# MINI_SAM_D51_018.net
KiCad netlist of a schematic drawn in EAGLE
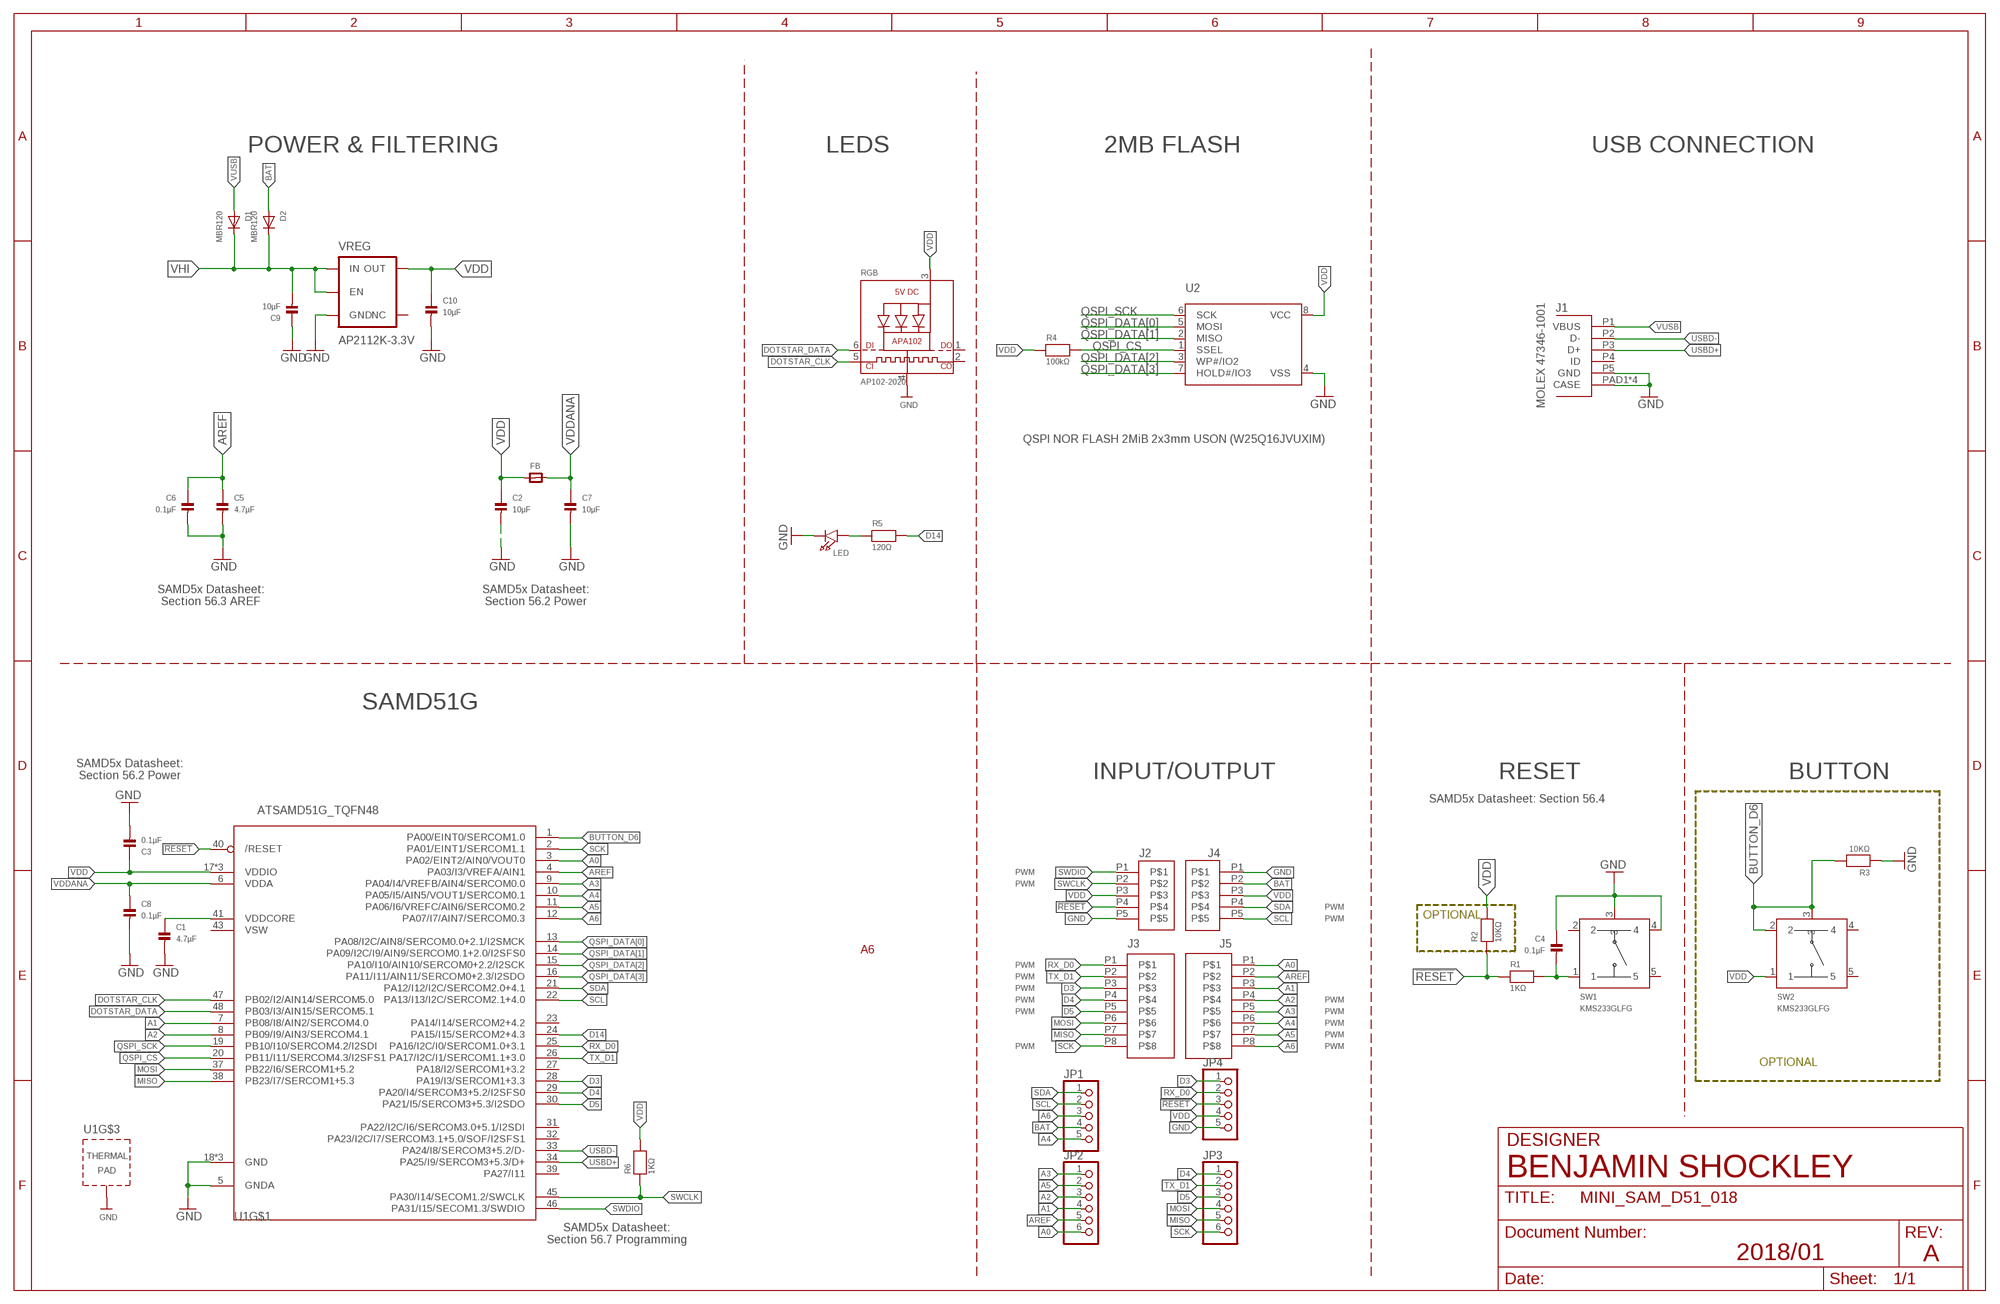
[diagram p0: schematic, sheet 1]

(export (version "E")
  (design (tool "Eeschema 10.0.6"))
  (components
    (comp (ref "C1")
      (value "4.7µF")
      (footprint "eagle-import:_0603MP")
      (libsource (lib "eagle-import") (part "CAP_CERAMIC_0603MP"))
    )
    (comp (ref "C2")
      (value "10µF")
      (footprint "eagle-import:_0603MP")
      (libsource (lib "eagle-import") (part "CAP_CERAMIC_0603MP"))
    )
    (comp (ref "C3")
      (value "0.1µF")
      (footprint "eagle-import:_0603MP")
      (libsource (lib "eagle-import") (part "CAP_CERAMIC_0603MP"))
    )
    (comp (ref "C4")
      (value "0.1µF")
      (footprint "eagle-import:_0603MP")
      (libsource (lib "eagle-import") (part "CAP_CERAMIC_0603MP"))
    )
    (comp (ref "C5")
      (value "4.7µF")
      (footprint "eagle-import:_0603MP")
      (libsource (lib "eagle-import") (part "CAP_CERAMIC_0603MP"))
    )
    (comp (ref "C6")
      (value "0.1µF")
      (footprint "eagle-import:_0603MP")
      (libsource (lib "eagle-import") (part "CAP_CERAMIC_0603MP"))
    )
    (comp (ref "C7")
      (value "10µF")
      (footprint "eagle-import:_0603MP")
      (libsource (lib "eagle-import") (part "CAP_CERAMIC_0603MP"))
    )
    (comp (ref "C8")
      (value "0.1µF")
      (footprint "eagle-import:_0603MP")
      (libsource (lib "eagle-import") (part "CAP_CERAMIC_0603MP"))
    )
    (comp (ref "C9")
      (value "10µF")
      (footprint "eagle-import:_0603MP")
      (libsource (lib "eagle-import") (part "CAP_CERAMIC_0603MP"))
    )
    (comp (ref "C10")
      (value "10µF")
      (footprint "eagle-import:_0603MP")
      (libsource (lib "eagle-import") (part "CAP_CERAMIC_0603MP"))
    )
    (comp (ref "D1")
      (value "MBR120")
      (footprint "eagle-import:SOD-123FL")
      (libsource (lib "eagle-import") (part "DIODE_SOD-123FL"))
    )
    (comp (ref "D2")
      (value "MBR120")
      (footprint "eagle-import:SOD-123FL")
      (libsource (lib "eagle-import") (part "DIODE_SOD-123FL"))
    )
    (comp (ref "FB")
      (value "Impedence: 50 ohm @ 20 MHz, 220 Ohm @ 100 MHz; low DC resistance")
      (footprint "eagle-import:_0603MP")
      (libsource (lib "eagle-import") (part "FERRITE_0603MP"))
    )
    (comp (ref "J1")
      (value "MOLEX_47346-100147346")
      (footprint "eagle-import:MOLEX_47346-1001")
      (libsource (lib "eagle-import") (part "MOLEX_47346-100147346"))
    )
    (comp (ref "J2")
      (value "1X5_HEADER_1.27MMCAST")
      (footprint "eagle-import:1X5_HEADER_1.27MM_CASTELLATED")
      (libsource (lib "eagle-import") (part "1X5_HEADER_1.27MMCAST"))
    )
    (comp (ref "J3")
      (value "1X8_HEADER_1.27MMCAST")
      (footprint "eagle-import:1X8_HEADER_1.27MM_CASTELLATED")
      (libsource (lib "eagle-import") (part "1X8_HEADER_1.27MMCAST"))
    )
    (comp (ref "J4")
      (value "1X5_HEADER_1.27MMCAST")
      (footprint "eagle-import:1X5_HEADER_1.27MM_CASTELLATED")
      (libsource (lib "eagle-import") (part "1X5_HEADER_1.27MMCAST"))
    )
    (comp (ref "J5")
      (value "1X8_HEADER_1.27MMCAST")
      (footprint "eagle-import:1X8_HEADER_1.27MM_CASTELLATED")
      (libsource (lib "eagle-import") (part "1X8_HEADER_1.27MMCAST"))
    )
    (comp (ref "JP1")
      (value "PINHD-1X51X05_SMT")
      (footprint "eagle-import:1X05_SMT")
      (libsource (lib "eagle-import") (part "PINHD-1X51X05_SMT"))
    )
    (comp (ref "JP2")
      (value "PINHD-1X61X06_SMT")
      (footprint "eagle-import:1X06_SMT")
      (libsource (lib "eagle-import") (part "PINHD-1X61X06_SMT"))
    )
    (comp (ref "JP3")
      (value "PINHD-1X6REV")
      (footprint "eagle-import:1X06_SMT_REV")
      (libsource (lib "eagle-import") (part "PINHD-1X6REV"))
    )
    (comp (ref "JP4")
      (value "PINHD-1X51X05_SMT")
      (footprint "eagle-import:1X05_SMT")
      (libsource (lib "eagle-import") (part "PINHD-1X51X05_SMT"))
    )
    (comp (ref "LED")
      (value "VLRK31Q1R2-GS08")
      (footprint "eagle-import:REVERSE_MOUNT_LED")
      (libsource (lib "eagle-import") (part "REVERSEMOUNTLED"))
    )
    (comp (ref "R1")
      (value "1KΩ")
      (footprint "eagle-import:_0603MP")
      (libsource (lib "eagle-import") (part "RESISTOR_0603MP"))
    )
    (comp (ref "R2")
      (value "10KΩ")
      (footprint "eagle-import:_0603MP")
      (libsource (lib "eagle-import") (part "RESISTOR_0603MP"))
    )
    (comp (ref "R3")
      (value "10KΩ")
      (footprint "eagle-import:_0603MP")
      (libsource (lib "eagle-import") (part "RESISTOR_0603MP"))
    )
    (comp (ref "R4")
      (value "100kΩ")
      (footprint "eagle-import:_0603MP")
      (libsource (lib "eagle-import") (part "RESISTOR_0603MP"))
    )
    (comp (ref "R5")
      (value "120Ω")
      (footprint "eagle-import:_0603MP")
      (libsource (lib "eagle-import") (part "RESISTOR_0603MP"))
    )
    (comp (ref "R6")
      (value "1KΩ")
      (footprint "eagle-import:_0603MP")
      (libsource (lib "eagle-import") (part "RESISTOR_0603MP"))
    )
    (comp (ref "RGB")
      (value "AP102-2020")
      (footprint "eagle-import:APA102_2020")
      (libsource (lib "eagle-import") (part "APA1022020"))
    )
    (comp (ref "SW1")
      (value "KMS233GLFG")
      (footprint "eagle-import:KMS_SWITCH")
      (libsource (lib "eagle-import") (part "KMS_SWITCHKMS"))
    )
    (comp (ref "SW2")
      (value "KMS233GLFG")
      (footprint "eagle-import:KMS_SWITCH")
      (libsource (lib "eagle-import") (part "KMS_SWITCHKMS"))
    )
    (comp (ref "U$1")
      (value "A60")
      (footprint "eagle-import:A60")
      (libsource (lib "eagle-import") (part "A60"))
    )
    (comp (ref "U1")
      (value "ATSAMD51G_TQFN48")
      (footprint "eagle-import:TQFN48_7MM")
      (libsource (lib "eagle-import") (part "ATSAMD51G_TQFN48"))
    )
    (comp (ref "U2")
      (value "QSPI NOR FLASH 2MiB 2x3mm USON (W25Q16JVUXIM)")
      (footprint "eagle-import:USON8")
      (libsource (lib "eagle-import") (part "SPIFLASH_8PINUX"))
    )
    (comp (ref "VREG")
      (value "AP2112K-3.3V")
      (footprint "eagle-import:SOT23-5")
      (libsource (lib "eagle-import") (part "V_REG_AP2112K-3.3V"))
    )
  )
  (nets
    (net (code "1") (name "/VSW") (class "Default")
      (node (ref "U1") (pin "43") (pinfunction "VSW_43") (pintype "power_in"))
    )
    (net (code "2") (name "/~{RESET}") (class "Default")
      (node (ref "J2") (pin "P4") (pinfunction "P$4_P4") (pintype "bidirectional"))
      (node (ref "JP4") (pin "3") (pinfunction "3_3") (pintype "passive"))
      (node (ref "R1") (pin "1") (pinfunction "1_1") (pintype "passive"))
      (node (ref "R2") (pin "1") (pinfunction "1_1") (pintype "passive"))
      (node (ref "U1") (pin "40") (pinfunction "/RESET_40") (pintype "bidirectional"))
    )
    (net (code "3") (name "A0") (class "Default")
      (node (ref "J5") (pin "P1") (pinfunction "P$1_P1") (pintype "bidirectional"))
      (node (ref "JP2") (pin "6") (pinfunction "6_6") (pintype "passive"))
      (node (ref "U1") (pin "3") (pinfunction "PA02/EINT2/AIN0/VOUT0_3") (pintype "bidirectional"))
    )
    (net (code "4") (name "A1") (class "Default")
      (node (ref "J5") (pin "P3") (pinfunction "P$3_P3") (pintype "bidirectional"))
      (node (ref "JP2") (pin "4") (pinfunction "4_4") (pintype "passive"))
      (node (ref "U1") (pin "7") (pinfunction "PB08/I8/AIN2/SERCOM4.0_7") (pintype "bidirectional"))
    )
    (net (code "5") (name "A2") (class "Default")
      (node (ref "J5") (pin "P4") (pinfunction "P$4_P4") (pintype "bidirectional"))
      (node (ref "JP2") (pin "3") (pinfunction "3_3") (pintype "passive"))
      (node (ref "U1") (pin "8") (pinfunction "PB09/I9/AIN3/SERCOM4.1_8") (pintype "bidirectional"))
    )
    (net (code "6") (name "A3") (class "Default")
      (node (ref "J5") (pin "P5") (pinfunction "P$5_P5") (pintype "bidirectional"))
      (node (ref "JP2") (pin "1") (pinfunction "1_1") (pintype "passive"))
      (node (ref "U1") (pin "9") (pinfunction "PA04/I4/VREFB/AIN4/SERCOM0.0_9") (pintype "bidirectional"))
    )
    (net (code "7") (name "A4") (class "Default")
      (node (ref "J5") (pin "P6") (pinfunction "P$6_P6") (pintype "bidirectional"))
      (node (ref "JP1") (pin "5") (pinfunction "5_5") (pintype "passive"))
      (node (ref "U1") (pin "10") (pinfunction "PA05/I5/AIN5/VOUT1/SERCOM0.1_10") (pintype "bidirectional"))
    )
    (net (code "8") (name "A5") (class "Default")
      (node (ref "J5") (pin "P7") (pinfunction "P$7_P7") (pintype "bidirectional"))
      (node (ref "JP2") (pin "2") (pinfunction "2_2") (pintype "passive"))
      (node (ref "U1") (pin "11") (pinfunction "PA06/I6/VREFC/AIN6/SERCOM0.2_11") (pintype "bidirectional"))
    )
    (net (code "9") (name "A6") (class "Default")
      (node (ref "J5") (pin "P8") (pinfunction "P$8_P8") (pintype "bidirectional"))
      (node (ref "JP1") (pin "3") (pinfunction "3_3") (pintype "passive"))
      (node (ref "U1") (pin "12") (pinfunction "PA07/I7/AIN7/SERCOM0.3_12") (pintype "bidirectional"))
    )
    (net (code "10") (name "AREF") (class "Default")
      (node (ref "C5") (pin "1") (pinfunction "P$1_1") (pintype "passive"))
      (node (ref "C6") (pin "1") (pinfunction "P$1_1") (pintype "passive"))
      (node (ref "J5") (pin "P2") (pinfunction "P$2_P2") (pintype "bidirectional"))
      (node (ref "JP2") (pin "5") (pinfunction "5_5") (pintype "passive"))
      (node (ref "U1") (pin "4") (pinfunction "PA03/I3/VREFA/AIN1_4") (pintype "bidirectional"))
    )
    (net (code "11") (name "BAT") (class "Default")
      (node (ref "D2") (pin "A") (pinfunction "A_A") (pintype "passive"))
      (node (ref "J4") (pin "P2") (pinfunction "P$2_P2") (pintype "bidirectional"))
      (node (ref "JP1") (pin "4") (pinfunction "4_4") (pintype "passive"))
    )
    (net (code "12") (name "BUTTON_D6") (class "Default")
      (node (ref "R3") (pin "2") (pinfunction "2_2") (pintype "passive"))
      (node (ref "SW2") (pin "2") (pinfunction "2_2") (pintype "bidirectional"))
      (node (ref "SW2") (pin "3") (pinfunction "3_3") (pintype "bidirectional"))
      (node (ref "U1") (pin "1") (pinfunction "PA00/EINT0/SERCOM1.0_1") (pintype "bidirectional"))
    )
    (net (code "13") (name "D3") (class "Default")
      (node (ref "J3") (pin "P3") (pinfunction "P$3_P3") (pintype "bidirectional"))
      (node (ref "JP4") (pin "1") (pinfunction "1_1") (pintype "passive"))
      (node (ref "U1") (pin "28") (pinfunction "PA19/I3/SERCOM1+3.3_28") (pintype "bidirectional"))
    )
    (net (code "14") (name "D4") (class "Default")
      (node (ref "J3") (pin "P4") (pinfunction "P$4_P4") (pintype "bidirectional"))
      (node (ref "JP3") (pin "1") (pinfunction "1_1") (pintype "passive"))
      (node (ref "U1") (pin "29") (pinfunction "PA20/I4/SERCOM3+5.2/I2SFS0_29") (pintype "bidirectional"))
    )
    (net (code "15") (name "D5") (class "Default")
      (node (ref "J3") (pin "P5") (pinfunction "P$5_P5") (pintype "bidirectional"))
      (node (ref "JP3") (pin "3") (pinfunction "3_3") (pintype "passive"))
      (node (ref "U1") (pin "30") (pinfunction "PA21/I5/SERCOM3+5.3/I2SDO_30") (pintype "bidirectional"))
    )
    (net (code "16") (name "D14") (class "Default")
      (node (ref "R5") (pin "2") (pinfunction "2_2") (pintype "passive"))
      (node (ref "U1") (pin "24") (pinfunction "PA15/I15/SERCOM2+4.3_24") (pintype "bidirectional"))
    )
    (net (code "17") (name "DOTSTAR_CLK") (class "Default")
      (node (ref "RGB") (pin "5") (pinfunction "CKI_5") (pintype "input"))
      (node (ref "U1") (pin "47") (pinfunction "PB02/I2/AIN14/SERCOM5.0_47") (pintype "bidirectional"))
    )
    (net (code "18") (name "DOTSTAR_DATA") (class "Default")
      (node (ref "RGB") (pin "6") (pinfunction "DI_6") (pintype "input"))
      (node (ref "U1") (pin "48") (pinfunction "PB03/I3/AIN15/SERCOM5.1_48") (pintype "bidirectional"))
    )
    (net (code "19") (name "GND") (class "Default")
      (node (ref "C1") (pin "2") (pinfunction "P$2_2") (pintype "passive"))
      (node (ref "C10") (pin "2") (pinfunction "P$2_2") (pintype "passive"))
      (node (ref "C2") (pin "2") (pinfunction "P$2_2") (pintype "passive"))
      (node (ref "C3") (pin "2") (pinfunction "P$2_2") (pintype "passive"))
      (node (ref "C4") (pin "1") (pinfunction "P$1_1") (pintype "passive"))
      (node (ref "C5") (pin "2") (pinfunction "P$2_2") (pintype "passive"))
      (node (ref "C6") (pin "2") (pinfunction "P$2_2") (pintype "passive"))
      (node (ref "C7") (pin "2") (pinfunction "P$2_2") (pintype "passive"))
      (node (ref "C8") (pin "2") (pinfunction "P$2_2") (pintype "passive"))
      (node (ref "C9") (pin "1") (pinfunction "P$1_1") (pintype "passive"))
      (node (ref "J1") (pin "P5") (pinfunction "GND_P5") (pintype "power_in"))
      (node (ref "J1") (pin "PAD1") (pinfunction "CASE_PAD1") (pintype "bidirectional"))
      (node (ref "J1") (pin "PAD2") (pinfunction "CASE_PAD2") (pintype "bidirectional"))
      (node (ref "J1") (pin "PAD3") (pinfunction "CASE_PAD3") (pintype "bidirectional"))
      (node (ref "J1") (pin "PAD4") (pinfunction "CASE_PAD4") (pintype "bidirectional"))
      (node (ref "J2") (pin "P5") (pinfunction "P$5_P5") (pintype "bidirectional"))
      (node (ref "J4") (pin "P1") (pinfunction "P$1_P1") (pintype "bidirectional"))
      (node (ref "JP4") (pin "5") (pinfunction "5_5") (pintype "passive"))
      (node (ref "LED") (pin "C") (pinfunction "C_C") (pintype "passive"))
      (node (ref "R3") (pin "1") (pinfunction "1_1") (pintype "passive"))
      (node (ref "RGB") (pin "4") (pinfunction "GND_4") (pintype "power_in"))
      (node (ref "SW1") (pin "3") (pinfunction "3_3") (pintype "bidirectional"))
      (node (ref "SW1") (pin "4") (pinfunction "4_4") (pintype "bidirectional"))
      (node (ref "U1") (pin "18") (pinfunction "GND_18") (pintype "power_in"))
      (node (ref "U1") (pin "35") (pinfunction "GND_35") (pintype "power_in"))
      (node (ref "U1") (pin "42") (pinfunction "GND_42") (pintype "power_in"))
      (node (ref "U1") (pin "5") (pinfunction "GNDA_5") (pintype "power_in"))
      (node (ref "U1") (pin "THERMAL") (pinfunction "TP_THERMAL") (pintype "power_in"))
      (node (ref "U2") (pin "4") (pinfunction "VSS_4") (pintype "bidirectional"))
      (node (ref "VREG") (pin "2") (pinfunction "GND_2") (pintype "input"))
    )
    (net (code "20") (name "MISO") (class "Default")
      (node (ref "J3") (pin "P7") (pinfunction "P$7_P7") (pintype "bidirectional"))
      (node (ref "JP3") (pin "5") (pinfunction "5_5") (pintype "passive"))
      (node (ref "U1") (pin "38") (pinfunction "PB23/I7/SERCOM1+5.3_38") (pintype "bidirectional"))
    )
    (net (code "21") (name "MOSI") (class "Default")
      (node (ref "J3") (pin "P6") (pinfunction "P$6_P6") (pintype "bidirectional"))
      (node (ref "JP3") (pin "4") (pinfunction "4_4") (pintype "passive"))
      (node (ref "U1") (pin "37") (pinfunction "PB22/I6/SERCOM1+5.2_37") (pintype "bidirectional"))
    )
    (net (code "22") (name "Net-(C1-P$1)") (class "Default")
      (node (ref "C1") (pin "1") (pinfunction "P$1_1") (pintype "passive"))
      (node (ref "U1") (pin "41") (pinfunction "VDDCORE_41") (pintype "power_in"))
    )
    (net (code "23") (name "Net-(C4-P$2)") (class "Default")
      (node (ref "C4") (pin "2") (pinfunction "P$2_2") (pintype "passive"))
      (node (ref "R1") (pin "2") (pinfunction "2_2") (pintype "passive"))
      (node (ref "SW1") (pin "1") (pinfunction "1_1") (pintype "bidirectional"))
    )
    (net (code "24") (name "Net-(LED-PadA)") (class "Default")
      (node (ref "LED") (pin "A") (pinfunction "A_A") (pintype "passive"))
      (node (ref "R5") (pin "1") (pinfunction "1_1") (pintype "passive"))
    )
    (net (code "25") (name "QSPI_CS") (class "Default")
      (node (ref "R4") (pin "2") (pinfunction "2_2") (pintype "passive"))
      (node (ref "U1") (pin "20") (pinfunction "PB11/I11/SERCOM4.3/I2SFS1_20") (pintype "bidirectional"))
      (node (ref "U2") (pin "1") (pinfunction "SSEL_1") (pintype "bidirectional"))
    )
    (net (code "26") (name "QSPI_DATA[0]") (class "Default")
      (node (ref "U1") (pin "13") (pinfunction "PA08/I2C/AIN8/SERCOM0.0+2.1/I2SMCK_13") (pintype "bidirectional"))
      (node (ref "U2") (pin "5") (pinfunction "MOSI_5") (pintype "bidirectional"))
    )
    (net (code "27") (name "QSPI_DATA[1]") (class "Default")
      (node (ref "U1") (pin "14") (pinfunction "PA09/I2C/I9/AIN9/SERCOM0.1+2.0/I2SFS0_14") (pintype "bidirectional"))
      (node (ref "U2") (pin "2") (pinfunction "MISO_2") (pintype "bidirectional"))
    )
    (net (code "28") (name "QSPI_DATA[2]") (class "Default")
      (node (ref "U1") (pin "15") (pinfunction "PA10/I10/AIN10/SERCOM0+2.2/I2SCK_15") (pintype "bidirectional"))
      (node (ref "U2") (pin "3") (pinfunction "WP#/IO2_3") (pintype "bidirectional"))
    )
    (net (code "29") (name "QSPI_DATA[3]") (class "Default")
      (node (ref "U1") (pin "16") (pinfunction "PA11/I11/AIN11/SERCOM0+2.3/I2SDO_16") (pintype "bidirectional"))
      (node (ref "U2") (pin "7") (pinfunction "HOLD#/IO3_7") (pintype "bidirectional"))
    )
    (net (code "30") (name "QSPI_SCK") (class "Default")
      (node (ref "U1") (pin "19") (pinfunction "PB10/I10/SERCOM4.2/I2SDI_19") (pintype "bidirectional"))
      (node (ref "U2") (pin "6") (pinfunction "SCK_6") (pintype "bidirectional"))
    )
    (net (code "31") (name "RX_D0") (class "Default")
      (node (ref "J3") (pin "P1") (pinfunction "P$1_P1") (pintype "bidirectional"))
      (node (ref "JP4") (pin "2") (pinfunction "2_2") (pintype "passive"))
      (node (ref "U1") (pin "25") (pinfunction "PA16/I2C/I0/SERCOM1.0+3.1_25") (pintype "bidirectional"))
    )
    (net (code "32") (name "SCK") (class "Default")
      (node (ref "J3") (pin "P8") (pinfunction "P$8_P8") (pintype "bidirectional"))
      (node (ref "JP3") (pin "6") (pinfunction "6_6") (pintype "passive"))
      (node (ref "U1") (pin "2") (pinfunction "PA01/EINT1/SERCOM1.1_2") (pintype "bidirectional"))
    )
    (net (code "33") (name "SCL") (class "Default")
      (node (ref "J4") (pin "P5") (pinfunction "P$5_P5") (pintype "bidirectional"))
      (node (ref "JP1") (pin "2") (pinfunction "2_2") (pintype "passive"))
      (node (ref "U1") (pin "22") (pinfunction "PA13/I13/I2C/SERCOM2.1+4.0_22") (pintype "bidirectional"))
    )
    (net (code "34") (name "SDA") (class "Default")
      (node (ref "J4") (pin "P4") (pinfunction "P$4_P4") (pintype "bidirectional"))
      (node (ref "JP1") (pin "1") (pinfunction "1_1") (pintype "passive"))
      (node (ref "U1") (pin "21") (pinfunction "PA12/I12/I2C/SERCOM2.0+4.1_21") (pintype "bidirectional"))
    )
    (net (code "35") (name "SWCLK") (class "Default")
      (node (ref "J2") (pin "P2") (pinfunction "P$2_P2") (pintype "bidirectional"))
      (node (ref "R6") (pin "1") (pinfunction "1_1") (pintype "passive"))
      (node (ref "U1") (pin "45") (pinfunction "PA30/I14/SECOM1.2/SWCLK_45") (pintype "bidirectional"))
    )
    (net (code "36") (name "SWDIO") (class "Default")
      (node (ref "J2") (pin "P1") (pinfunction "P$1_P1") (pintype "bidirectional"))
      (node (ref "U1") (pin "46") (pinfunction "PA31/I15/SECOM1.3/SWDIO_46") (pintype "bidirectional"))
    )
    (net (code "37") (name "TX_D1") (class "Default")
      (node (ref "J3") (pin "P2") (pinfunction "P$2_P2") (pintype "bidirectional"))
      (node (ref "JP3") (pin "2") (pinfunction "2_2") (pintype "passive"))
      (node (ref "U1") (pin "26") (pinfunction "PA17/I2C/I1/SERCOM1.1+3.0_26") (pintype "bidirectional"))
    )
    (net (code "38") (name "USBD+") (class "Default")
      (node (ref "J1") (pin "P3") (pinfunction "D+_P3") (pintype "bidirectional"))
      (node (ref "U1") (pin "34") (pinfunction "PA25/I9/SERCOM3+5.3/D+_34") (pintype "bidirectional"))
    )
    (net (code "39") (name "USBD-") (class "Default")
      (node (ref "J1") (pin "P2") (pinfunction "D-_P2") (pintype "bidirectional"))
      (node (ref "U1") (pin "33") (pinfunction "PA24/I8/SERCOM3+5.2/D-_33") (pintype "bidirectional"))
    )
    (net (code "40") (name "VDD") (class "Default")
      (node (ref "C10") (pin "1") (pinfunction "P$1_1") (pintype "passive"))
      (node (ref "C2") (pin "1") (pinfunction "P$1_1") (pintype "passive"))
      (node (ref "C3") (pin "1") (pinfunction "P$1_1") (pintype "passive"))
      (node (ref "FB") (pin "1") (pinfunction "P$1_1") (pintype "passive"))
      (node (ref "J2") (pin "P3") (pinfunction "P$3_P3") (pintype "bidirectional"))
      (node (ref "J4") (pin "P3") (pinfunction "P$3_P3") (pintype "bidirectional"))
      (node (ref "JP4") (pin "4") (pinfunction "4_4") (pintype "passive"))
      (node (ref "R2") (pin "2") (pinfunction "2_2") (pintype "passive"))
      (node (ref "R4") (pin "1") (pinfunction "1_1") (pintype "passive"))
      (node (ref "R6") (pin "2") (pinfunction "2_2") (pintype "passive"))
      (node (ref "RGB") (pin "3") (pinfunction "VDD_3") (pintype "power_in"))
      (node (ref "SW2") (pin "1") (pinfunction "1_1") (pintype "bidirectional"))
      (node (ref "U1") (pin "17") (pinfunction "VDDIO_17") (pintype "power_in"))
      (node (ref "U1") (pin "36") (pinfunction "VDDIO_36") (pintype "power_in"))
      (node (ref "U1") (pin "44") (pinfunction "VDDIO_44") (pintype "power_in"))
      (node (ref "U2") (pin "8") (pinfunction "VCC_8") (pintype "bidirectional"))
      (node (ref "VREG") (pin "5") (pinfunction "OUT_5") (pintype "passive"))
    )
    (net (code "41") (name "VDDANA") (class "Default")
      (node (ref "C7") (pin "1") (pinfunction "P$1_1") (pintype "passive"))
      (node (ref "C8") (pin "1") (pinfunction "P$1_1") (pintype "passive"))
      (node (ref "FB") (pin "2") (pinfunction "P$2_2") (pintype "passive"))
      (node (ref "U1") (pin "6") (pinfunction "VDDA_6") (pintype "power_in"))
    )
    (net (code "42") (name "VHI") (class "Default")
      (node (ref "C9") (pin "2") (pinfunction "P$2_2") (pintype "passive"))
      (node (ref "D1") (pin "C") (pinfunction "C_C") (pintype "passive"))
      (node (ref "D2") (pin "C") (pinfunction "C_C") (pintype "passive"))
      (node (ref "VREG") (pin "1") (pinfunction "IN_1") (pintype "input"))
      (node (ref "VREG") (pin "3") (pinfunction "EN_3") (pintype "input"))
    )
    (net (code "43") (name "VUSB") (class "Default")
      (node (ref "D1") (pin "A") (pinfunction "A_A") (pintype "passive"))
      (node (ref "J1") (pin "P1") (pinfunction "VBUS_P1") (pintype "power_in"))
    )
    (net (code "44") (name "unconnected-(J1-ID-PadP4)") (class "Default")
      (node (ref "J1") (pin "P4") (pinfunction "ID_P4") (pintype "bidirectional"))
    )
    (net (code "45") (name "unconnected-(RGB-CKO-Pad2)") (class "Default")
      (node (ref "RGB") (pin "2") (pinfunction "CKO_2") (pintype "output"))
    )
    (net (code "46") (name "unconnected-(RGB-DO-Pad1)") (class "Default")
      (node (ref "RGB") (pin "1") (pinfunction "DO_1") (pintype "output"))
    )
    (net (code "47") (name "unconnected-(SW1-Pad2)") (class "Default")
      (node (ref "SW1") (pin "2") (pinfunction "2_2") (pintype "bidirectional"))
    )
    (net (code "48") (name "unconnected-(SW1-Pad5)") (class "Default")
      (node (ref "SW1") (pin "5") (pinfunction "5_5") (pintype "bidirectional"))
    )
    (net (code "49") (name "unconnected-(SW2-Pad4)") (class "Default")
      (node (ref "SW2") (pin "4") (pinfunction "4_4") (pintype "bidirectional"))
    )
    (net (code "50") (name "unconnected-(SW2-Pad5)") (class "Default")
      (node (ref "SW2") (pin "5") (pinfunction "5_5") (pintype "bidirectional"))
    )
    (net (code "51") (name "unconnected-(U1A-PA14{slash}I14{slash}SERCOM2+4.2-Pad23)") (class "Default")
      (node (ref "U1") (pin "23") (pinfunction "PA14/I14/SERCOM2+4.2_23") (pintype "bidirectional"))
    )
    (net (code "52") (name "unconnected-(U1A-PA18{slash}I2{slash}SERCOM1+3.2-Pad27)") (class "Default")
      (node (ref "U1") (pin "27") (pinfunction "PA18/I2/SERCOM1+3.2_27") (pintype "bidirectional"))
    )
    (net (code "53") (name "unconnected-(U1A-PA22{slash}I2C{slash}I6{slash}SERCOM3.0+5.1{slash}I2SDI-Pad31)") (class "Default")
      (node (ref "U1") (pin "31") (pinfunction "PA22/I2C/I6/SERCOM3.0+5.1/I2SDI_31") (pintype "bidirectional"))
    )
    (net (code "54") (name "unconnected-(U1A-PA23{slash}I2C{slash}I7{slash}SERCOM3.1+5.0{slash}SOF{slash}I2SFS1-Pad32)") (class "Default")
      (node (ref "U1") (pin "32") (pinfunction "PA23/I2C/I7/SERCOM3.1+5.0/SOF/I2SFS1_32") (pintype "bidirectional"))
    )
    (net (code "55") (name "unconnected-(U1A-PA27{slash}I11-Pad39)") (class "Default")
      (node (ref "U1") (pin "39") (pinfunction "PA27/I11_39") (pintype "bidirectional"))
    )
    (net (code "56") (name "unconnected-(VREG-NC-Pad4)") (class "Default")
      (node (ref "VREG") (pin "4") (pinfunction "NC_4") (pintype "input"))
    )
  )
)
